# Desk_Clock_v1_1_old.net
KiCad netlist of a schematic drawn in EAGLE
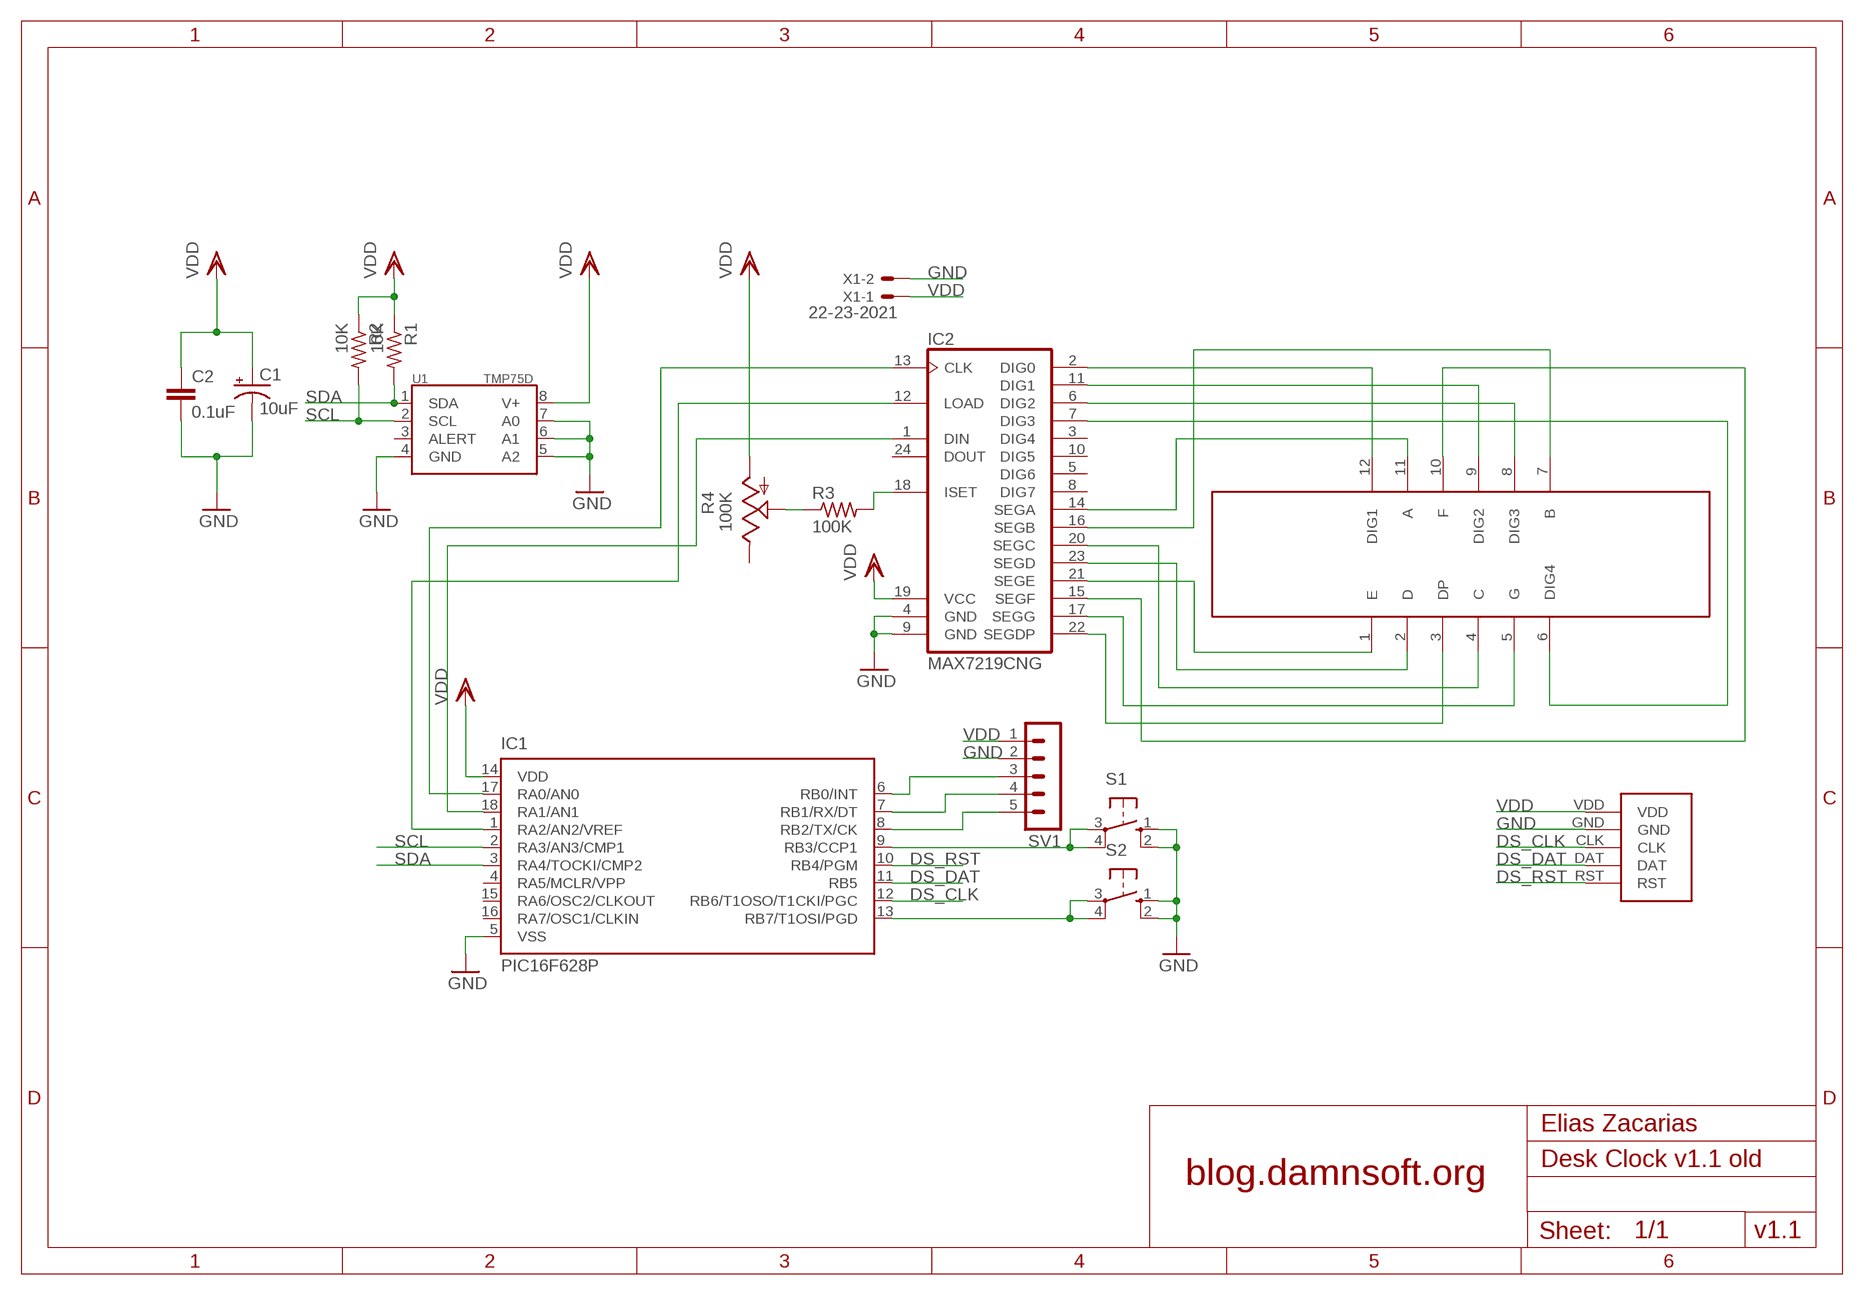
[diagram p0: schematic, sheet 1]

(export (version "E")
  (design (tool "Eeschema 10.0.6"))
  (components
    (comp (ref "C1")
      (value "10uF")
      (footprint "eagle-import:E2-4")
      (libsource (lib "eagle-import") (part "CPOL-USE2-4"))
    )
    (comp (ref "C2")
      (value "0.1uF")
      (footprint "eagle-import:C025-025X050")
      (libsource (lib "eagle-import") (part "C-EU025-025X050"))
    )
    (comp (ref "IC1")
      (value "PIC16F628P")
      (footprint "eagle-import:DIL18")
      (fields (field (name "MF") "MICROCHIP") (field (name "MPN") "PIC16F628-04I/P"))
      (libsource (lib "eagle-import") (part "PIC16F62P8"))
    )
    (comp (ref "IC2")
      (value "MAX7219CNG")
      (footprint "eagle-import:DIL24-3")
      (fields (field (name "MF") "MAXIM"))
      (libsource (lib "eagle-import") (part "MAX7219CNG"))
    )
    (comp (ref "R1")
      (value "10K")
      (footprint "eagle-import:0207_10")
      (libsource (lib "eagle-import") (part "R-US_0207/10"))
    )
    (comp (ref "R2")
      (value "10K")
      (footprint "eagle-import:0207_10")
      (libsource (lib "eagle-import") (part "R-US_0207/10"))
    )
    (comp (ref "R3")
      (value "100K")
      (footprint "eagle-import:0207_10")
      (libsource (lib "eagle-import") (part "R-US_0207/10"))
    )
    (comp (ref "R4")
      (value "100K")
      (footprint "eagle-import:CA6V")
      (libsource (lib "eagle-import") (part "TRIM_US-CA6V"))
    )
    (comp (ref "S1")
      (value "10-XX")
      (footprint "eagle-import:B3F-10XX")
      (fields (field (name "MPN") "B3F-1000"))
      (libsource (lib "eagle-import") (part "10-XX"))
    )
    (comp (ref "S2")
      (value "10-XX")
      (footprint "eagle-import:B3F-10XX")
      (fields (field (name "MPN") "B3F-1000"))
      (libsource (lib "eagle-import") (part "10-XX"))
    )
    (comp (ref "SV1")
      (value "MA05-1")
      (footprint "eagle-import:MA05-1")
      (libsource (lib "eagle-import") (part "MA05-1"))
    )
    (comp (ref "U$1")
      (value "NFD-5642BX")
      (footprint "eagle-import:DISPLAY")
      (libsource (lib "eagle-import") (part "NFD-5642BX"))
    )
    (comp (ref "U$2")
      (value "DS1302_BOARD")
      (footprint "eagle-import:DS1302_BOARD")
      (libsource (lib "eagle-import") (part "DS1302_BOARD"))
    )
    (comp (ref "U1")
      (value "TMP75D")
      (footprint "eagle-import:SO-08")
      (libsource (lib "eagle-import") (part "TMP75D"))
    )
    (comp (ref "X1")
      (value "22-23-2021")
      (footprint "eagle-import:22-23-2021")
      (fields (field (name "MF") "MOLEX"))
      (libsource (lib "eagle-import") (part "22-23-2021"))
    )
  )
  (nets
    (net (code "1") (name "/DS_CLK") (class "Default")
      (node (ref "IC1") (pin "12") (pinfunction "RB6/T1OSO/T1CKI/PGC_12") (pintype "bidirectional"))
      (node (ref "U$2") (pin "CLK") (pinfunction "CLK_CLK") (pintype "bidirectional"))
    )
    (net (code "2") (name "/DS_DAT") (class "Default")
      (node (ref "IC1") (pin "11") (pinfunction "RB5_11") (pintype "bidirectional"))
      (node (ref "U$2") (pin "DAT") (pinfunction "DAT_DAT") (pintype "bidirectional"))
    )
    (net (code "3") (name "/DS_RST") (class "Default")
      (node (ref "IC1") (pin "10") (pinfunction "RB4/PGM_10") (pintype "bidirectional"))
      (node (ref "U$2") (pin "RST") (pinfunction "RST_RST") (pintype "bidirectional"))
    )
    (net (code "4") (name "/SCL") (class "Default")
      (node (ref "IC1") (pin "2") (pinfunction "RA3/AN3/CMP1_2") (pintype "bidirectional"))
      (node (ref "R2") (pin "2") (pinfunction "2_2") (pintype "passive"))
      (node (ref "U1") (pin "2") (pinfunction "SCL_2") (pintype "bidirectional"))
    )
    (net (code "5") (name "/SDA") (class "Default")
      (node (ref "IC1") (pin "3") (pinfunction "RA4/TOCKI/CMP2_3") (pintype "bidirectional"))
      (node (ref "R1") (pin "2") (pinfunction "2_2") (pintype "passive"))
      (node (ref "U1") (pin "1") (pinfunction "SDA_1") (pintype "bidirectional"))
    )
    (net (code "6") (name "GND") (class "Default")
      (node (ref "C1") (pin "-") (pinfunction "-_-") (pintype "passive"))
      (node (ref "C2") (pin "2") (pinfunction "2_2") (pintype "passive"))
      (node (ref "IC1") (pin "5") (pinfunction "VSS_5") (pintype "power_in"))
      (node (ref "IC2") (pin "4") (pinfunction "GND_4") (pintype "power_in"))
      (node (ref "IC2") (pin "9") (pinfunction "GND_9") (pintype "power_in"))
      (node (ref "S1") (pin "1") (pinfunction "S_1") (pintype "passive"))
      (node (ref "S1") (pin "2") (pinfunction "S1_2") (pintype "passive"))
      (node (ref "S2") (pin "1") (pinfunction "S_1") (pintype "passive"))
      (node (ref "S2") (pin "2") (pinfunction "S1_2") (pintype "passive"))
      (node (ref "SV1") (pin "2") (pinfunction "2_2") (pintype "passive"))
      (node (ref "U$2") (pin "GND") (pinfunction "GND_GND") (pintype "bidirectional"))
      (node (ref "U1") (pin "4") (pinfunction "GND_4") (pintype "bidirectional"))
      (node (ref "U1") (pin "5") (pinfunction "A2_5") (pintype "bidirectional"))
      (node (ref "U1") (pin "6") (pinfunction "A1_6") (pintype "bidirectional"))
      (node (ref "U1") (pin "7") (pinfunction "A0_7") (pintype "bidirectional"))
      (node (ref "X1") (pin "2") (pinfunction "S_2") (pintype "passive"))
    )
    (net (code "7") (name "Net-(IC1-RA0{slash}AN0)") (class "Default")
      (node (ref "IC1") (pin "17") (pinfunction "RA0/AN0_17") (pintype "bidirectional"))
      (node (ref "IC2") (pin "13") (pinfunction "CLK_13") (pintype "input"))
    )
    (net (code "8") (name "Net-(IC1-RA1{slash}AN1)") (class "Default")
      (node (ref "IC1") (pin "18") (pinfunction "RA1/AN1_18") (pintype "bidirectional"))
      (node (ref "IC2") (pin "1") (pinfunction "DIN_1") (pintype "input"))
    )
    (net (code "9") (name "Net-(IC1-RA2{slash}AN2{slash}VREF)") (class "Default")
      (node (ref "IC1") (pin "1") (pinfunction "RA2/AN2/VREF_1") (pintype "bidirectional"))
      (node (ref "IC2") (pin "12") (pinfunction "LOAD_12") (pintype "input"))
    )
    (net (code "10") (name "Net-(IC1-RB0{slash}INT)") (class "Default")
      (node (ref "IC1") (pin "6") (pinfunction "RB0/INT_6") (pintype "bidirectional"))
      (node (ref "SV1") (pin "3") (pinfunction "3_3") (pintype "passive"))
    )
    (net (code "11") (name "Net-(IC1-RB1{slash}RX{slash}DT)") (class "Default")
      (node (ref "IC1") (pin "7") (pinfunction "RB1/RX/DT_7") (pintype "bidirectional"))
      (node (ref "SV1") (pin "4") (pinfunction "4_4") (pintype "passive"))
    )
    (net (code "12") (name "Net-(IC1-RB2{slash}TX{slash}CK)") (class "Default")
      (node (ref "IC1") (pin "8") (pinfunction "RB2/TX/CK_8") (pintype "bidirectional"))
      (node (ref "SV1") (pin "5") (pinfunction "5_5") (pintype "passive"))
    )
    (net (code "13") (name "Net-(IC1-RB3{slash}CCP1)") (class "Default")
      (node (ref "IC1") (pin "9") (pinfunction "RB3/CCP1_9") (pintype "bidirectional"))
      (node (ref "S1") (pin "3") (pinfunction "P_3") (pintype "passive"))
      (node (ref "S1") (pin "4") (pinfunction "P1_4") (pintype "passive"))
    )
    (net (code "14") (name "Net-(IC1-RB7{slash}T1OSI{slash}PGD)") (class "Default")
      (node (ref "IC1") (pin "13") (pinfunction "RB7/T1OSI/PGD_13") (pintype "bidirectional"))
      (node (ref "S2") (pin "3") (pinfunction "P_3") (pintype "passive"))
      (node (ref "S2") (pin "4") (pinfunction "P1_4") (pintype "passive"))
    )
    (net (code "15") (name "Net-(IC2-DIG0)") (class "Default")
      (node (ref "IC2") (pin "2") (pinfunction "DIG0_2") (pintype "output"))
      (node (ref "U$1") (pin "12") (pinfunction "DIG1_12") (pintype "bidirectional"))
    )
    (net (code "16") (name "Net-(IC2-DIG1)") (class "Default")
      (node (ref "IC2") (pin "11") (pinfunction "DIG1_11") (pintype "output"))
      (node (ref "U$1") (pin "9") (pinfunction "DIG2_9") (pintype "bidirectional"))
    )
    (net (code "17") (name "Net-(IC2-DIG2)") (class "Default")
      (node (ref "IC2") (pin "6") (pinfunction "DIG2_6") (pintype "output"))
      (node (ref "U$1") (pin "8") (pinfunction "DIG3_8") (pintype "bidirectional"))
    )
    (net (code "18") (name "Net-(IC2-DIG3)") (class "Default")
      (node (ref "IC2") (pin "7") (pinfunction "DIG3_7") (pintype "output"))
      (node (ref "U$1") (pin "6") (pinfunction "DIG4_6") (pintype "bidirectional"))
    )
    (net (code "19") (name "Net-(IC2-ISET)") (class "Default")
      (node (ref "IC2") (pin "18") (pinfunction "ISET_18") (pintype "input"))
      (node (ref "R3") (pin "2") (pinfunction "2_2") (pintype "passive"))
    )
    (net (code "20") (name "Net-(IC2-SEGA)") (class "Default")
      (node (ref "IC2") (pin "14") (pinfunction "SEGA_14") (pintype "output"))
      (node (ref "U$1") (pin "11") (pinfunction "A_11") (pintype "bidirectional"))
    )
    (net (code "21") (name "Net-(IC2-SEGB)") (class "Default")
      (node (ref "IC2") (pin "16") (pinfunction "SEGB_16") (pintype "output"))
      (node (ref "U$1") (pin "7") (pinfunction "B_7") (pintype "bidirectional"))
    )
    (net (code "22") (name "Net-(IC2-SEGC)") (class "Default")
      (node (ref "IC2") (pin "20") (pinfunction "SEGC_20") (pintype "output"))
      (node (ref "U$1") (pin "4") (pinfunction "C_4") (pintype "bidirectional"))
    )
    (net (code "23") (name "Net-(IC2-SEGD)") (class "Default")
      (node (ref "IC2") (pin "23") (pinfunction "SEGD_23") (pintype "output"))
      (node (ref "U$1") (pin "2") (pinfunction "D_2") (pintype "bidirectional"))
    )
    (net (code "24") (name "Net-(IC2-SEGDP)") (class "Default")
      (node (ref "IC2") (pin "22") (pinfunction "SEGDP_22") (pintype "output"))
      (node (ref "U$1") (pin "3") (pinfunction "DP_3") (pintype "bidirectional"))
    )
    (net (code "25") (name "Net-(IC2-SEGE)") (class "Default")
      (node (ref "IC2") (pin "21") (pinfunction "SEGE_21") (pintype "output"))
      (node (ref "U$1") (pin "1") (pinfunction "E_1") (pintype "bidirectional"))
    )
    (net (code "26") (name "Net-(IC2-SEGF)") (class "Default")
      (node (ref "IC2") (pin "15") (pinfunction "SEGF_15") (pintype "output"))
      (node (ref "U$1") (pin "10") (pinfunction "F_10") (pintype "bidirectional"))
    )
    (net (code "27") (name "Net-(IC2-SEGG)") (class "Default")
      (node (ref "IC2") (pin "17") (pinfunction "SEGG_17") (pintype "output"))
      (node (ref "U$1") (pin "5") (pinfunction "G_5") (pintype "bidirectional"))
    )
    (net (code "28") (name "Net-(R3-Pad1)") (class "Default")
      (node (ref "R3") (pin "1") (pinfunction "1_1") (pintype "passive"))
      (node (ref "R4") (pin "S") (pinfunction "S_S") (pintype "passive"))
    )
    (net (code "29") (name "VDD") (class "Default")
      (node (ref "C1") (pin "+") (pinfunction "+_+") (pintype "passive"))
      (node (ref "C2") (pin "1") (pinfunction "1_1") (pintype "passive"))
      (node (ref "IC1") (pin "14") (pinfunction "VDD_14") (pintype "power_in"))
      (node (ref "IC2") (pin "19") (pinfunction "VCC_19") (pintype "power_in"))
      (node (ref "R1") (pin "1") (pinfunction "1_1") (pintype "passive"))
      (node (ref "R2") (pin "1") (pinfunction "1_1") (pintype "passive"))
      (node (ref "R4") (pin "A") (pinfunction "A_A") (pintype "passive"))
      (node (ref "SV1") (pin "1") (pinfunction "1_1") (pintype "passive"))
      (node (ref "U$2") (pin "VDD") (pinfunction "VDD_VDD") (pintype "bidirectional"))
      (node (ref "U1") (pin "8") (pinfunction "V+_8") (pintype "bidirectional"))
      (node (ref "X1") (pin "1") (pinfunction "S_1") (pintype "passive"))
    )
    (net (code "30") (name "unconnected-(IC1-RA5{slash}MCLR{slash}VPP-Pad4)") (class "Default")
      (node (ref "IC1") (pin "4") (pinfunction "RA5/MCLR/VPP_4") (pintype "bidirectional"))
    )
    (net (code "31") (name "unconnected-(IC1-RA6{slash}OSC2{slash}CLKOUT-Pad15)") (class "Default")
      (node (ref "IC1") (pin "15") (pinfunction "RA6/OSC2/CLKOUT_15") (pintype "bidirectional"))
    )
    (net (code "32") (name "unconnected-(IC1-RA7{slash}OSC1{slash}CLKIN-Pad16)") (class "Default")
      (node (ref "IC1") (pin "16") (pinfunction "RA7/OSC1/CLKIN_16") (pintype "bidirectional"))
    )
    (net (code "33") (name "unconnected-(IC2-DIG4-Pad3)") (class "Default")
      (node (ref "IC2") (pin "3") (pinfunction "DIG4_3") (pintype "output"))
    )
    (net (code "34") (name "unconnected-(IC2-DIG5-Pad10)") (class "Default")
      (node (ref "IC2") (pin "10") (pinfunction "DIG5_10") (pintype "output"))
    )
    (net (code "35") (name "unconnected-(IC2-DIG6-Pad5)") (class "Default")
      (node (ref "IC2") (pin "5") (pinfunction "DIG6_5") (pintype "output"))
    )
    (net (code "36") (name "unconnected-(IC2-DIG7-Pad8)") (class "Default")
      (node (ref "IC2") (pin "8") (pinfunction "DIG7_8") (pintype "output"))
    )
    (net (code "37") (name "unconnected-(IC2-DOUT-Pad24)") (class "Default")
      (node (ref "IC2") (pin "24") (pinfunction "DOUT_24") (pintype "output"))
    )
    (net (code "38") (name "unconnected-(R4-PadE)") (class "Default")
      (node (ref "R4") (pin "E") (pinfunction "E_E") (pintype "passive"))
    )
    (net (code "39") (name "unconnected-(U1-ALERT-Pad3)") (class "Default")
      (node (ref "U1") (pin "3") (pinfunction "ALERT_3") (pintype "bidirectional"))
    )
  )
)
